# IO_Expander.net
KiCad netlist of a schematic drawn in Altium Designer
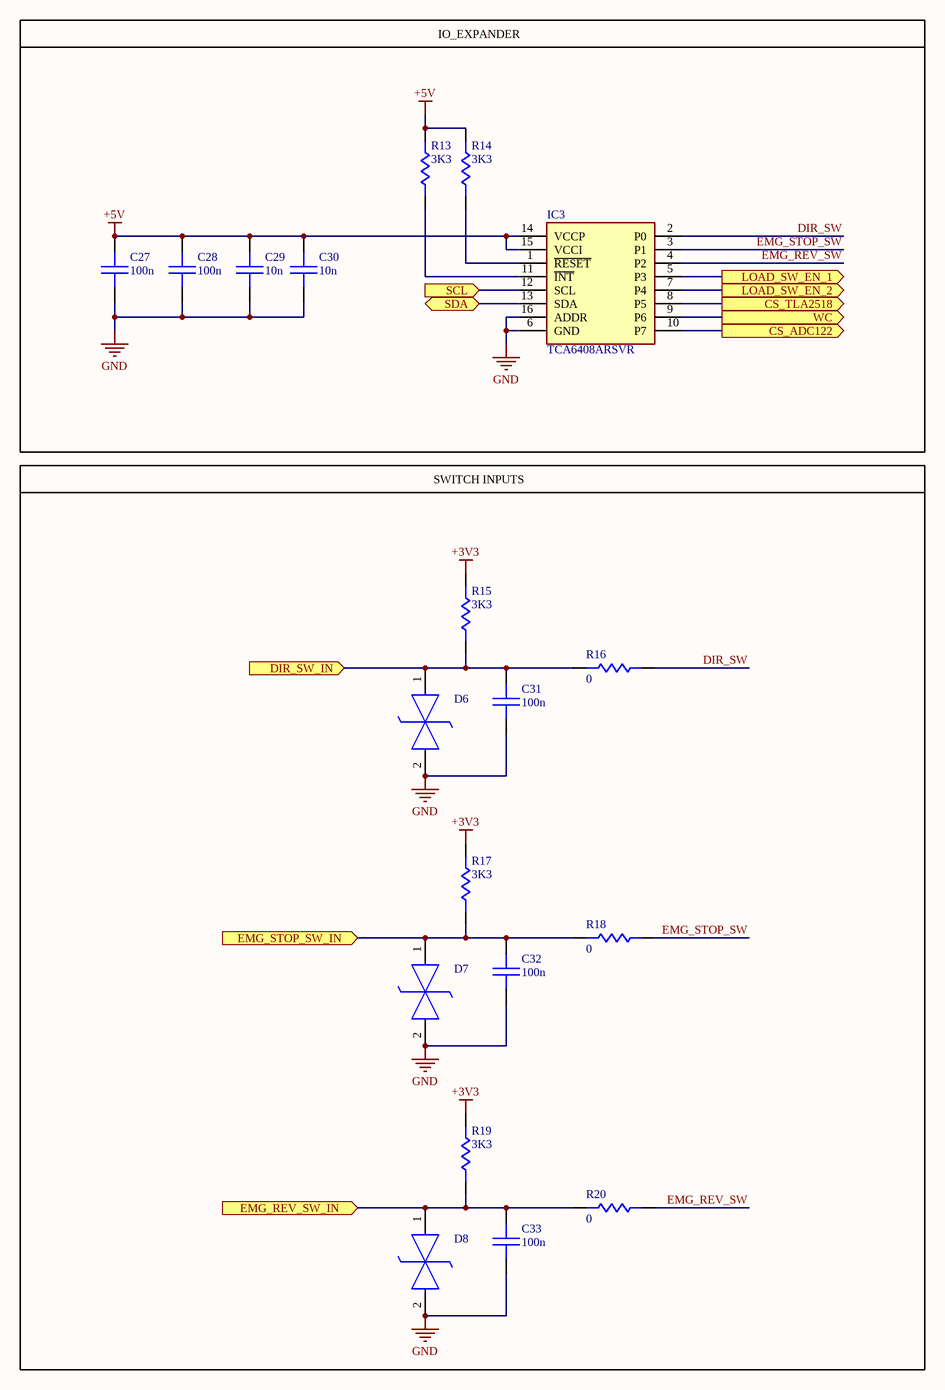
[diagram p0: IO_Expander.SchDoc]

(export (version "E")
  (design (tool "Eeschema 10.0.6"))
  (components
    (comp (ref "C27")
      (value "100n")
      (footprint "C_0603")
      (description "SMD Chip Capacitor")
      (libsource (lib "My_Integrated_Lib") (part "CAP"))
    )
    (comp (ref "C28")
      (value "100n")
      (footprint "C_0603")
      (description "SMD Chip Capacitor")
      (libsource (lib "My_Integrated_Lib") (part "CAP"))
    )
    (comp (ref "C29")
      (value "10n")
      (footprint "C_0603")
      (description "SMD Chip Capacitor")
      (libsource (lib "My_Integrated_Lib") (part "CAP"))
    )
    (comp (ref "C30")
      (value "10n")
      (footprint "C_0603")
      (description "SMD Chip Capacitor")
      (libsource (lib "My_Integrated_Lib") (part "CAP"))
    )
    (comp (ref "C31")
      (value "100n")
      (footprint "C_0603")
      (description "SMD Chip Capacitor")
      (libsource (lib "My_Integrated_Lib") (part "CAP"))
    )
    (comp (ref "C32")
      (value "100n")
      (footprint "C_0603")
      (description "SMD Chip Capacitor")
      (libsource (lib "My_Integrated_Lib") (part "CAP"))
    )
    (comp (ref "C33")
      (value "100n")
      (footprint "C_0603")
      (description "SMD Chip Capacitor")
      (libsource (lib "My_Integrated_Lib") (part "CAP"))
    )
    (comp (ref "D6")
      (value "PESD3V3Y1BSFYL")
      (footprint "PMEG3005AESFYL")
      (description "Diode ESD (Bi-directional)")
      (fields (field (name "MOUSER PART NUMBER") "771-PESD3V3Y1BSFYL"))
      (libsource (lib "My_Integrated_Lib") (part "PESD3V3Y1BSFYL"))
    )
    (comp (ref "D7")
      (value "PESD3V3Y1BSFYL")
      (footprint "PMEG3005AESFYL")
      (description "Diode ESD (Bi-directional)")
      (fields (field (name "MOUSER PART NUMBER") "771-PESD3V3Y1BSFYL"))
      (libsource (lib "My_Integrated_Lib") (part "PESD3V3Y1BSFYL"))
    )
    (comp (ref "D8")
      (value "PESD3V3Y1BSFYL")
      (footprint "PMEG3005AESFYL")
      (description "Diode ESD (Bi-directional)")
      (fields (field (name "MOUSER PART NUMBER") "771-PESD3V3Y1BSFYL"))
      (libsource (lib "My_Integrated_Lib") (part "PESD3V3Y1BSFYL"))
    )
    (comp (ref "IC3")
      (value "TCA6408ARSVR")
      (footprint "QFN40P180X260X55-16N")
      (description "Integrated Circuit")
      (fields (field (name "MOUSER PART NUMBER") "595-TCA6408ARSVR"))
      (libsource (lib "My_Integrated_Lib") (part "TCA6408ARSVR"))
    )
    (comp (ref "R13")
      (value "3K3")
      (footprint "R_0603")
      (description "SMD Chip Resistor")
      (libsource (lib "My_Integrated_Lib") (part "RES"))
    )
    (comp (ref "R14")
      (value "3K3")
      (footprint "R_0603")
      (description "SMD Chip Resistor")
      (libsource (lib "My_Integrated_Lib") (part "RES"))
    )
    (comp (ref "R15")
      (value "3K3")
      (footprint "R_0603")
      (description "SMD Chip Resistor")
      (libsource (lib "My_Integrated_Lib") (part "RES"))
    )
    (comp (ref "R16")
      (value "0")
      (footprint "R_0603")
      (description "SMD Chip Resistor")
      (libsource (lib "My_Integrated_Lib") (part "RES"))
    )
    (comp (ref "R17")
      (value "3K3")
      (footprint "R_0603")
      (description "SMD Chip Resistor")
      (libsource (lib "My_Integrated_Lib") (part "RES"))
    )
    (comp (ref "R18")
      (value "0")
      (footprint "R_0603")
      (description "SMD Chip Resistor")
      (libsource (lib "My_Integrated_Lib") (part "RES"))
    )
    (comp (ref "R19")
      (value "3K3")
      (footprint "R_0603")
      (description "SMD Chip Resistor")
      (libsource (lib "My_Integrated_Lib") (part "RES"))
    )
    (comp (ref "R20")
      (value "0")
      (footprint "R_0603")
      (description "SMD Chip Resistor")
      (libsource (lib "My_Integrated_Lib") (part "RES"))
    )
  )
  (nets
    (net (code "1") (name "+3V3") (class "Default")
      (node (ref "R15") (pin "2") (pinfunction "2_2") (pintype "passive"))
      (node (ref "R17") (pin "2") (pinfunction "2_2") (pintype "passive"))
      (node (ref "R19") (pin "2") (pinfunction "2_2") (pintype "passive"))
    )
    (net (code "2") (name "+5V") (class "Default")
      (node (ref "C27") (pin "1") (pinfunction "1_1") (pintype "passive"))
      (node (ref "C28") (pin "1") (pinfunction "1_1") (pintype "passive"))
      (node (ref "C29") (pin "1") (pinfunction "1_1") (pintype "passive"))
      (node (ref "C30") (pin "1") (pinfunction "1_1") (pintype "passive"))
      (node (ref "IC3") (pin "14") (pinfunction "VCCP_14") (pintype "passive"))
      (node (ref "IC3") (pin "15") (pinfunction "VCCI_15") (pintype "passive"))
      (node (ref "R13") (pin "2") (pinfunction "2_2") (pintype "passive"))
      (node (ref "R14") (pin "2") (pinfunction "2_2") (pintype "passive"))
    )
    (net (code "3") (name "/CS_ADC122") (class "Default")
      (node (ref "IC3") (pin "10") (pinfunction "P7_10") (pintype "passive"))
    )
    (net (code "4") (name "/CS_TLA2518") (class "Default")
      (node (ref "IC3") (pin "8") (pinfunction "P5_8") (pintype "passive"))
    )
    (net (code "5") (name "/DIR_SW") (class "Default")
      (node (ref "IC3") (pin "2") (pinfunction "P0_2") (pintype "passive"))
      (node (ref "R16") (pin "1") (pinfunction "1_1") (pintype "passive"))
    )
    (net (code "6") (name "/DIR_SW_IN") (class "Default")
      (node (ref "C31") (pin "1") (pinfunction "1_1") (pintype "passive"))
      (node (ref "D6") (pin "1") (pinfunction "K1_1") (pintype "passive"))
      (node (ref "R15") (pin "1") (pinfunction "1_1") (pintype "passive"))
      (node (ref "R16") (pin "2") (pinfunction "2_2") (pintype "passive"))
    )
    (net (code "7") (name "/EMG_REV_SW") (class "Default")
      (node (ref "IC3") (pin "4") (pinfunction "P2_4") (pintype "passive"))
      (node (ref "R20") (pin "1") (pinfunction "1_1") (pintype "passive"))
    )
    (net (code "8") (name "/EMG_REV_SW_IN") (class "Default")
      (node (ref "C33") (pin "1") (pinfunction "1_1") (pintype "passive"))
      (node (ref "D8") (pin "1") (pinfunction "K1_1") (pintype "passive"))
      (node (ref "R19") (pin "1") (pinfunction "1_1") (pintype "passive"))
      (node (ref "R20") (pin "2") (pinfunction "2_2") (pintype "passive"))
    )
    (net (code "9") (name "/EMG_STOP_SW") (class "Default")
      (node (ref "IC3") (pin "3") (pinfunction "P1_3") (pintype "passive"))
      (node (ref "R18") (pin "1") (pinfunction "1_1") (pintype "passive"))
    )
    (net (code "10") (name "/EMG_STOP_SW_IN") (class "Default")
      (node (ref "C32") (pin "1") (pinfunction "1_1") (pintype "passive"))
      (node (ref "D7") (pin "1") (pinfunction "K1_1") (pintype "passive"))
      (node (ref "R17") (pin "1") (pinfunction "1_1") (pintype "passive"))
      (node (ref "R18") (pin "2") (pinfunction "2_2") (pintype "passive"))
    )
    (net (code "11") (name "/LOAD_SW_EN_1") (class "Default")
      (node (ref "IC3") (pin "5") (pinfunction "P3_5") (pintype "passive"))
    )
    (net (code "12") (name "/LOAD_SW_EN_2") (class "Default")
      (node (ref "IC3") (pin "7") (pinfunction "P4_7") (pintype "passive"))
    )
    (net (code "13") (name "/SCL") (class "Default")
      (node (ref "IC3") (pin "12") (pinfunction "SCL_12") (pintype "passive"))
    )
    (net (code "14") (name "/SDA") (class "Default")
      (node (ref "IC3") (pin "13") (pinfunction "SDA_13") (pintype "passive"))
    )
    (net (code "15") (name "/WC") (class "Default")
      (node (ref "IC3") (pin "9") (pinfunction "P6_9") (pintype "passive"))
    )
    (net (code "16") (name "GND") (class "Default")
      (node (ref "C27") (pin "2") (pinfunction "2_2") (pintype "passive"))
      (node (ref "C28") (pin "2") (pinfunction "2_2") (pintype "passive"))
      (node (ref "C29") (pin "2") (pinfunction "2_2") (pintype "passive"))
      (node (ref "C30") (pin "2") (pinfunction "2_2") (pintype "passive"))
      (node (ref "C31") (pin "2") (pinfunction "2_2") (pintype "passive"))
      (node (ref "C32") (pin "2") (pinfunction "2_2") (pintype "passive"))
      (node (ref "C33") (pin "2") (pinfunction "2_2") (pintype "passive"))
      (node (ref "D6") (pin "2") (pinfunction "K2_2") (pintype "passive"))
      (node (ref "D7") (pin "2") (pinfunction "K2_2") (pintype "passive"))
      (node (ref "D8") (pin "2") (pinfunction "K2_2") (pintype "passive"))
      (node (ref "IC3") (pin "16") (pinfunction "ADDR_16") (pintype "passive"))
      (node (ref "IC3") (pin "6") (pinfunction "GND_6") (pintype "passive"))
    )
    (net (code "17") (name "Net-(IC3-~{INT})") (class "Default")
      (node (ref "IC3") (pin "11") (pinfunction "~{INT}_11") (pintype "passive"))
      (node (ref "R13") (pin "1") (pinfunction "1_1") (pintype "passive"))
    )
    (net (code "18") (name "Net-(IC3-~{RESET})") (class "Default")
      (node (ref "IC3") (pin "1") (pinfunction "~{RESET}_1") (pintype "passive"))
      (node (ref "R14") (pin "1") (pinfunction "1_1") (pintype "passive"))
    )
  )
)
